# MCU_1_12.net
KiCad netlist of a schematic drawn in Altium Designer
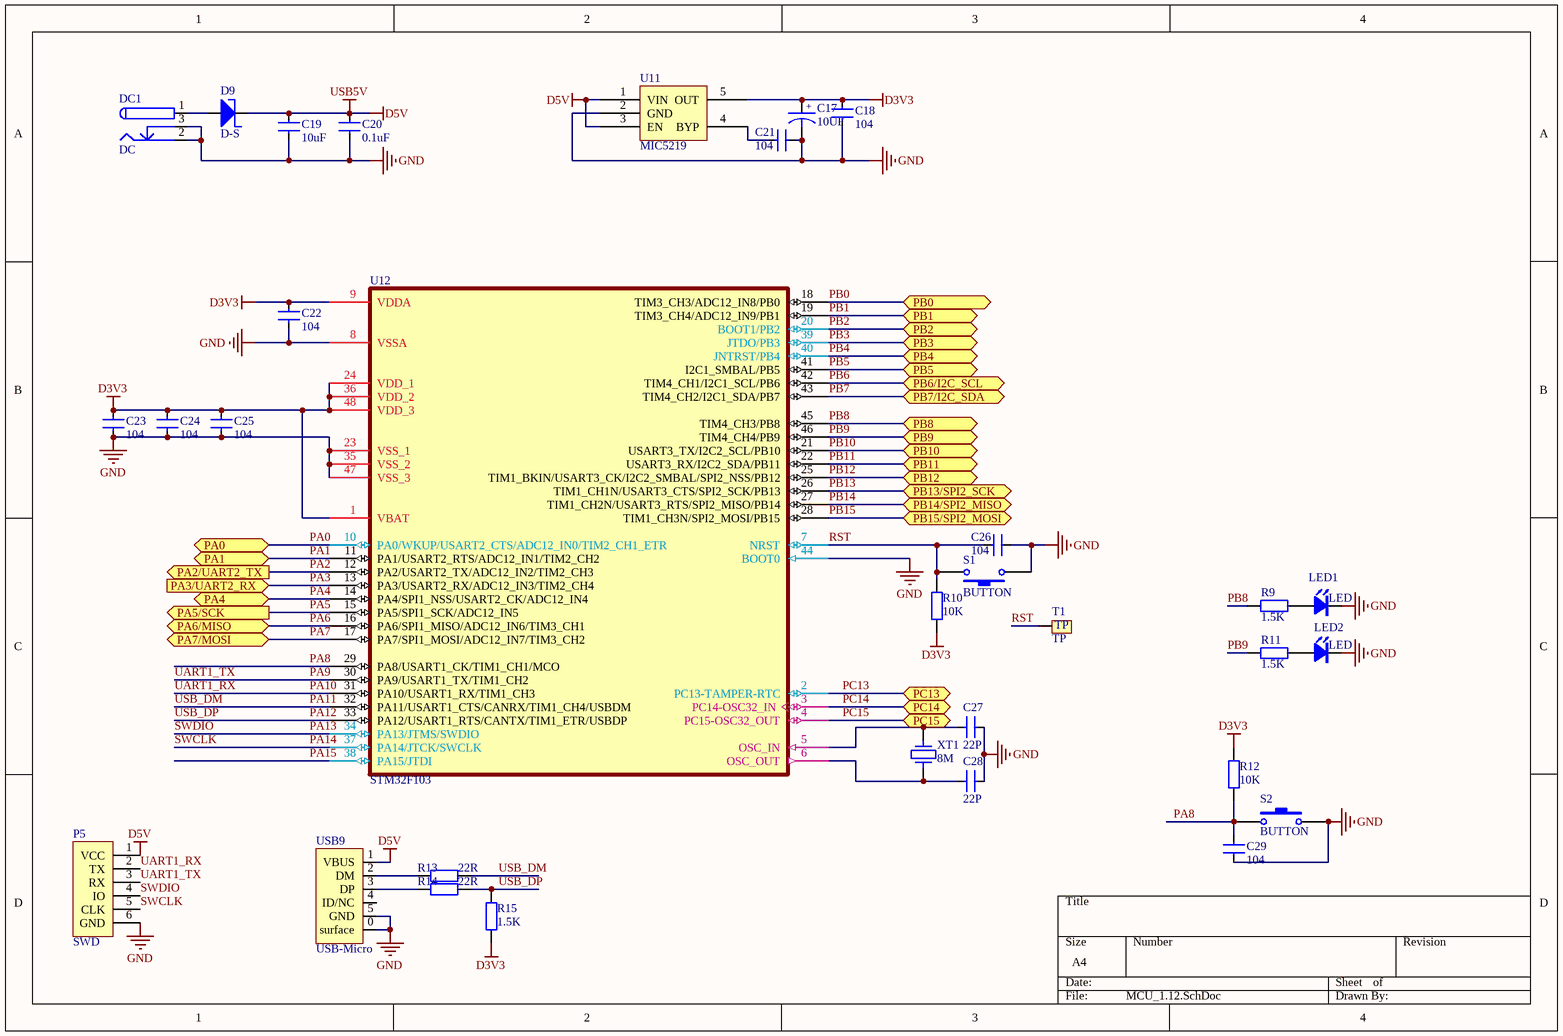
[diagram p0: MCU_1.12.SchDoc]

(export (version "E")
  (design (tool "Eeschema 10.0.6"))
  (components
    (comp (ref "C17")
      (value "10UF")
      (footprint "3216C")
      (description "钽电容")
      (libsource (lib "lib_AD") (part "CAP-T"))
    )
    (comp (ref "C18")
      (value "104")
      (footprint "0603C")
      (description "普通小电容")
      (libsource (lib "lib_GMDZ") (part "CAP"))
    )
    (comp (ref "C19")
      (value "10uF")
      (footprint "0805C")
      (description "普通小电容")
      (libsource (lib "lib_AD") (part "CAP"))
    )
    (comp (ref "C20")
      (value "0.1uF")
      (footprint "0402C")
      (description "普通小电容")
      (libsource (lib "lib_AD") (part "CAP"))
    )
    (comp (ref "C21")
      (value "104")
      (footprint "0603C")
      (description "普通小电容")
      (libsource (lib "lib_GMDZ") (part "CAP"))
    )
    (comp (ref "C22")
      (value "104")
      (footprint "0603C")
      (description "普通小电容")
      (libsource (lib "lib_GMDZ") (part "CAP"))
    )
    (comp (ref "C23")
      (value "104")
      (footprint "0603C")
      (description "普通小电容")
      (libsource (lib "lib_GMDZ") (part "CAP"))
    )
    (comp (ref "C24")
      (value "104")
      (footprint "0603C")
      (description "普通小电容")
      (libsource (lib "lib_GMDZ") (part "CAP"))
    )
    (comp (ref "C25")
      (value "104")
      (footprint "0603C")
      (description "普通小电容")
      (libsource (lib "lib_GMDZ") (part "CAP"))
    )
    (comp (ref "C26")
      (value "104")
      (footprint "0603C")
      (description "普通小电容")
      (libsource (lib "lib_AD") (part "CAP"))
    )
    (comp (ref "C27")
      (value "22P")
      (footprint "0603C")
      (description "普通小电容")
      (libsource (lib "lib_AD") (part "CAP"))
    )
    (comp (ref "C28")
      (value "22P")
      (footprint "0603C")
      (description "普通小电容")
      (libsource (lib "lib_AD") (part "CAP"))
    )
    (comp (ref "C29")
      (value "104")
      (footprint "0603C")
      (description "普通小电容")
      (libsource (lib "lib_AD") (part "CAP"))
    )
    (comp (ref "D9")
      (value "D-S")
      (footprint "SOD123")
      (description "肖特基二极管")
      (libsource (lib "lib_AD") (part "D-S"))
    )
    (comp (ref "DC1")
      (value "DC")
      (footprint "DC005")
      (description "圆形电源接口")
      (libsource (lib "lib_AD") (part "DC00X"))
    )
    (comp (ref "LED1") (value "LED") (footprint "0805D") (libsource (lib "lib_AD") (part "LED")))
    (comp (ref "LED2") (value "LED") (footprint "0805D") (libsource (lib "lib_AD") (part "LED")))
    (comp (ref "P5")
      (value "SWD")
      (footprint "HDR1X6")
      (description "单片机端")
      (libsource (lib "lib_AD") (part "SWD"))
    )
    (comp (ref "R9")
      (value "1.5K")
      (footprint "0603R")
      (description "普通电阻")
      (libsource (lib "lib_AD") (part "RES"))
    )
    (comp (ref "R10")
      (value "10K")
      (footprint "0603R")
      (description "普通电阻")
      (libsource (lib "") (part "RES_1"))
    )
    (comp (ref "R11")
      (value "1.5K")
      (footprint "0603R")
      (description "普通电阻")
      (libsource (lib "lib_AD") (part "RES"))
    )
    (comp (ref "R12")
      (value "10K")
      (footprint "0603R")
      (description "普通电阻")
      (libsource (lib "") (part "RES_3"))
    )
    (comp (ref "R13")
      (value "22R")
      (footprint "0603R")
      (description "普通电阻")
      (libsource (lib "") (part "RES_2"))
    )
    (comp (ref "R14")
      (value "22R")
      (footprint "0603R")
      (description "普通电阻")
      (libsource (lib "") (part "RES_2"))
    )
    (comp (ref "R15")
      (value "1.5K")
      (footprint "0603R")
      (description "普通电阻")
      (libsource (lib "") (part "RES_3"))
    )
    (comp (ref "S1") (value "BUTTON") (footprint "SW-3X4X2") (libsource (lib "lib_AD") (part "BUTTON")))
    (comp (ref "S2") (value "BUTTON") (footprint "SW-3X4X2") (libsource (lib "lib_AD") (part "BUTTON")))
    (comp (ref "T1")
      (value "TP")
      (footprint "TP1")
      (description "testpoint")
      (libsource (lib "lib_AD") (part "TP"))
    )
    (comp (ref "U11") (value "MIC5219") (footprint "SOT23-5") (libsource (lib "lib_GMDZ") (part "MIC5219")))
    (comp (ref "U12")
      (value "STM32F103")
      (footprint "LQFP48")
      (libsource (lib "lib_GMDZ") (part "STM32F103"))
    )
    (comp (ref "USB9")
      (value "USB-Micro")
      (footprint "USB-Micro-2")
      (description "USB 1.1, Right Angle, SMT, A Type, Plug, 4 Position, Natural")
      (fields (field (name "PUBLISHER") "Altium Limited"))
      (libsource (lib "lib_AD") (part "USB-Micro"))
    )
    (comp (ref "XT1")
      (value "8M")
      (footprint "5032")
      (description "晶振")
      (libsource (lib "lib_GMDZ") (part "XT"))
    )
  )
  (nets
    (net (code "4") (name "/PA0") (class "Default")
      (node (ref "U12") (pin "10") (pinfunction "PA0/WKUP/USART2_CTS/ADC12_IN0/TIM2_CH1_ETR_10") (pintype "bidirectional"))
    )
    (net (code "5") (name "/PA1") (class "Default")
      (node (ref "U12") (pin "11") (pinfunction "PA1/USART2_RTS/ADC12_IN1/TIM2_CH2_11") (pintype "bidirectional"))
    )
    (net (code "6") (name "/PA2") (class "Default")
      (node (ref "U12") (pin "12") (pinfunction "PA2/USART2_TX/ADC12_IN2/TIM2_CH3_12") (pintype "bidirectional"))
    )
    (net (code "7") (name "/PA3") (class "Default")
      (node (ref "U12") (pin "13") (pinfunction "PA3/USART2_RX/ADC12_IN3/TIM2_CH4_13") (pintype "bidirectional"))
    )
    (net (code "8") (name "/PA4") (class "Default")
      (node (ref "U12") (pin "14") (pinfunction "PA4/SPI1_NSS/USART2_CK/ADC12_IN4_14") (pintype "bidirectional"))
    )
    (net (code "9") (name "/PA5") (class "Default")
      (node (ref "U12") (pin "15") (pinfunction "PA5/SPI1_SCK/ADC12_IN5_15") (pintype "bidirectional"))
    )
    (net (code "10") (name "/PA6") (class "Default")
      (node (ref "U12") (pin "16") (pinfunction "PA6/SPI1_MISO/ADC12_IN6/TIM3_CH1_16") (pintype "bidirectional"))
    )
    (net (code "11") (name "/PA7") (class "Default")
      (node (ref "U12") (pin "17") (pinfunction "PA7/SPI1_MOSI/ADC12_IN7/TIM3_CH2_17") (pintype "bidirectional"))
    )
    (net (code "12") (name "/PA8") (class "Default")
      (node (ref "C29") (pin "2") (pinfunction "2_2") (pintype "passive"))
      (node (ref "R12") (pin "2") (pinfunction "2_2") (pintype "passive"))
      (node (ref "S2") (pin "1") (pinfunction "1_1") (pintype "passive"))
      (node (ref "U12") (pin "29") (pinfunction "PA8/USART1_CK/TIM1_CH1/MCO_29") (pintype "bidirectional"))
    )
    (net (code "13") (name "/PA9") (class "Default")
      (node (ref "P5") (pin "3") (pinfunction "RX_3") (pintype "passive"))
      (node (ref "U12") (pin "30") (pinfunction "PA9/USART1_TX/TIM1_CH2_30") (pintype "bidirectional"))
    )
    (net (code "14") (name "/PA10") (class "Default")
      (node (ref "P5") (pin "2") (pinfunction "TX_2") (pintype "passive"))
      (node (ref "U12") (pin "31") (pinfunction "PA10/USART1_RX/TIM1_CH3_31") (pintype "bidirectional"))
    )
    (net (code "15") (name "/PA11") (class "Default")
      (node (ref "R13") (pin "1") (pinfunction "1_1") (pintype "passive"))
      (node (ref "U12") (pin "32") (pinfunction "PA11/USART1_CTS/CANRX/TIM1_CH4/USBDM_32") (pintype "bidirectional"))
    )
    (net (code "16") (name "/PA12") (class "Default")
      (node (ref "R14") (pin "1") (pinfunction "1_1") (pintype "passive"))
      (node (ref "R15") (pin "1") (pinfunction "1_1") (pintype "passive"))
      (node (ref "U12") (pin "33") (pinfunction "PA12/USART1_RTS/CANTX/TIM1_ETR/USBDP_33") (pintype "bidirectional"))
    )
    (net (code "17") (name "/PA13") (class "Default")
      (node (ref "P5") (pin "4") (pinfunction "IO_4") (pintype "passive"))
      (node (ref "U12") (pin "34") (pinfunction "PA13/JTMS/SWDIO_34") (pintype "bidirectional"))
    )
    (net (code "18") (name "/PA14") (class "Default")
      (node (ref "P5") (pin "5") (pinfunction "CLK_5") (pintype "passive"))
      (node (ref "U12") (pin "37") (pinfunction "PA14/JTCK/SWCLK_37") (pintype "bidirectional"))
    )
    (net (code "19") (name "/PA15") (class "Default")
      (node (ref "U12") (pin "38") (pinfunction "PA15/JTDI_38") (pintype "bidirectional"))
    )
    (net (code "20") (name "/PB0") (class "Default")
      (node (ref "U12") (pin "18") (pinfunction "TIM3_CH3/ADC12_IN8/PB0_18") (pintype "bidirectional"))
    )
    (net (code "21") (name "/PB1") (class "Default")
      (node (ref "U12") (pin "19") (pinfunction "TIM3_CH4/ADC12_IN9/PB1_19") (pintype "bidirectional"))
    )
    (net (code "22") (name "/PB2") (class "Default")
      (node (ref "U12") (pin "20") (pinfunction "BOOT1/PB2_20") (pintype "bidirectional"))
    )
    (net (code "23") (name "/PB3") (class "Default")
      (node (ref "U12") (pin "39") (pinfunction "JTDO/PB3_39") (pintype "bidirectional"))
    )
    (net (code "24") (name "/PB4") (class "Default")
      (node (ref "U12") (pin "40") (pinfunction "JNTRST/PB4_40") (pintype "bidirectional"))
    )
    (net (code "25") (name "/PB5") (class "Default")
      (node (ref "U12") (pin "41") (pinfunction "I2C1_SMBAL/PB5_41") (pintype "bidirectional"))
    )
    (net (code "26") (name "/PB6") (class "Default")
      (node (ref "U12") (pin "42") (pinfunction "TIM4_CH1/I2C1_SCL/PB6_42") (pintype "bidirectional"))
    )
    (net (code "27") (name "/PB7") (class "Default")
      (node (ref "U12") (pin "43") (pinfunction "TIM4_CH2/I2C1_SDA/PB7_43") (pintype "bidirectional"))
    )
    (net (code "28") (name "/PB8") (class "Default")
      (node (ref "R9") (pin "1") (pinfunction "1_1") (pintype "passive"))
      (node (ref "U12") (pin "45") (pinfunction "TIM4_CH3/PB8_45") (pintype "bidirectional"))
    )
    (net (code "29") (name "/PB9") (class "Default")
      (node (ref "R11") (pin "1") (pinfunction "1_1") (pintype "passive"))
      (node (ref "U12") (pin "46") (pinfunction "TIM4_CH4/PB9_46") (pintype "bidirectional"))
    )
    (net (code "30") (name "/PB10") (class "Default")
      (node (ref "U12") (pin "21") (pinfunction "USART3_TX/I2C2_SCL/PB10_21") (pintype "bidirectional"))
    )
    (net (code "31") (name "/PB11") (class "Default")
      (node (ref "U12") (pin "22") (pinfunction "USART3_RX/I2C2_SDA/PB11_22") (pintype "bidirectional"))
    )
    (net (code "32") (name "/PB12") (class "Default")
      (node (ref "U12") (pin "25") (pinfunction "TIM1_BKIN/USART3_CK/I2C2_SMBAL/SPI2_NSS/PB12_25") (pintype "bidirectional"))
    )
    (net (code "33") (name "/PB13") (class "Default")
      (node (ref "U12") (pin "26") (pinfunction "TIM1_CH1N/USART3_CTS/SPI2_SCK/PB13_26") (pintype "bidirectional"))
    )
    (net (code "34") (name "/PB14") (class "Default")
      (node (ref "U12") (pin "27") (pinfunction "TIM1_CH2N/USART3_RTS/SPI2_MISO/PB14_27") (pintype "bidirectional"))
    )
    (net (code "35") (name "/PB15") (class "Default")
      (node (ref "U12") (pin "28") (pinfunction "TIM1_CH3N/SPI2_MOSI/PB15_28") (pintype "bidirectional"))
    )
    (net (code "36") (name "/PC13") (class "Default")
      (node (ref "U12") (pin "2") (pinfunction "PC13-TAMPER-RTC_2") (pintype "bidirectional"))
    )
    (net (code "37") (name "/PC14") (class "Default")
      (node (ref "U12") (pin "3") (pinfunction "PC14-OSC32_IN_3") (pintype "bidirectional"))
    )
    (net (code "38") (name "/PC15") (class "Default")
      (node (ref "U12") (pin "4") (pinfunction "PC15-OSC32_OUT_4") (pintype "bidirectional"))
    )
    (net (code "39") (name "/RST") (class "Default")
      (node (ref "C26") (pin "1") (pinfunction "1_1") (pintype "passive"))
      (node (ref "R10") (pin "2") (pinfunction "2_2") (pintype "passive"))
      (node (ref "S1") (pin "2") (pinfunction "2_2") (pintype "passive"))
      (node (ref "T1") (pin "1") (pinfunction "1_1") (pintype "passive"))
      (node (ref "U12") (pin "7") (pinfunction "NRST_7") (pintype "bidirectional"))
    )
    (net (code "40") (name "D3V3") (class "Default")
      (node (ref "C17") (pin "1") (pinfunction "1_1") (pintype "passive"))
      (node (ref "C18") (pin "2") (pinfunction "2_2") (pintype "passive"))
      (node (ref "C22") (pin "2") (pinfunction "2_2") (pintype "passive"))
      (node (ref "C23") (pin "2") (pinfunction "2_2") (pintype "passive"))
      (node (ref "C24") (pin "1") (pinfunction "1_1") (pintype "passive"))
      (node (ref "C25") (pin "2") (pinfunction "2_2") (pintype "passive"))
      (node (ref "R10") (pin "1") (pinfunction "1_1") (pintype "passive"))
      (node (ref "R12") (pin "1") (pinfunction "1_1") (pintype "passive"))
      (node (ref "R15") (pin "2") (pinfunction "2_2") (pintype "passive"))
      (node (ref "U11") (pin "5") (pinfunction "OUT_5") (pintype "passive"))
      (node (ref "U12") (pin "1") (pinfunction "VBAT_1") (pintype "power_in"))
      (node (ref "U12") (pin "24") (pinfunction "VDD_1_24") (pintype "power_in"))
      (node (ref "U12") (pin "36") (pinfunction "VDD_2_36") (pintype "power_in"))
      (node (ref "U12") (pin "48") (pinfunction "VDD_3_48") (pintype "power_in"))
      (node (ref "U12") (pin "9") (pinfunction "VDDA_9") (pintype "power_in"))
    )
    (net (code "41") (name "D5V") (class "Default")
      (node (ref "C19") (pin "1") (pinfunction "1_1") (pintype "passive"))
      (node (ref "C20") (pin "1") (pinfunction "1_1") (pintype "passive"))
      (node (ref "D9") (pin "K") (pinfunction "2_K") (pintype "passive"))
      (node (ref "P5") (pin "1") (pinfunction "VCC_1") (pintype "passive"))
      (node (ref "U11") (pin "1") (pinfunction "VIN_1") (pintype "passive"))
      (node (ref "U11") (pin "3") (pinfunction "EN_3") (pintype "passive"))
      (node (ref "USB9") (pin "1") (pinfunction "VBUS_1") (pintype "power_in"))
    )
    (net (code "42") (name "GND") (class "Default")
      (node (ref "C17") (pin "2") (pinfunction "2_2") (pintype "passive"))
      (node (ref "C18") (pin "1") (pinfunction "1_1") (pintype "passive"))
      (node (ref "C19") (pin "2") (pinfunction "2_2") (pintype "passive"))
      (node (ref "C20") (pin "2") (pinfunction "2_2") (pintype "passive"))
      (node (ref "C21") (pin "2") (pinfunction "2_2") (pintype "passive"))
      (node (ref "C22") (pin "1") (pinfunction "1_1") (pintype "passive"))
      (node (ref "C23") (pin "1") (pinfunction "1_1") (pintype "passive"))
      (node (ref "C24") (pin "2") (pinfunction "2_2") (pintype "passive"))
      (node (ref "C25") (pin "1") (pinfunction "1_1") (pintype "passive"))
      (node (ref "C26") (pin "2") (pinfunction "2_2") (pintype "passive"))
      (node (ref "C27") (pin "2") (pinfunction "2_2") (pintype "passive"))
      (node (ref "C28") (pin "2") (pinfunction "2_2") (pintype "passive"))
      (node (ref "C29") (pin "1") (pinfunction "1_1") (pintype "passive"))
      (node (ref "DC1") (pin "2") (pinfunction "2_2") (pintype "power_in"))
      (node (ref "DC1") (pin "3") (pinfunction "3_3") (pintype "power_in"))
      (node (ref "LED1") (pin "K") (pinfunction "2_K") (pintype "passive"))
      (node (ref "LED2") (pin "K") (pinfunction "2_K") (pintype "passive"))
      (node (ref "P5") (pin "6") (pinfunction "GND_6") (pintype "passive"))
      (node (ref "S1") (pin "1") (pinfunction "1_1") (pintype "passive"))
      (node (ref "S2") (pin "2") (pinfunction "2_2") (pintype "passive"))
      (node (ref "U11") (pin "2") (pinfunction "GND_2") (pintype "passive"))
      (node (ref "U12") (pin "23") (pinfunction "VSS_1_23") (pintype "power_in"))
      (node (ref "U12") (pin "35") (pinfunction "VSS_2_35") (pintype "power_in"))
      (node (ref "U12") (pin "44") (pinfunction "BOOT0_44") (pintype "input"))
      (node (ref "U12") (pin "47") (pinfunction "VSS_3_47") (pintype "power_in"))
      (node (ref "U12") (pin "8") (pinfunction "VSSA_8") (pintype "power_in"))
      (node (ref "USB9") (pin "0") (pinfunction "surface_0") (pintype "passive"))
      (node (ref "USB9") (pin "5") (pinfunction "GND_5") (pintype "power_in"))
    )
    (net (code "43") (name "Net-(D9-1)") (class "Default")
      (node (ref "D9") (pin "A") (pinfunction "1_A") (pintype "passive"))
      (node (ref "DC1") (pin "1") (pinfunction "1_1") (pintype "power_in"))
    )
    (net (code "44") (name "Net-(LED1-1)") (class "Default")
      (node (ref "LED1") (pin "A") (pinfunction "1_A") (pintype "passive"))
      (node (ref "R9") (pin "2") (pinfunction "2_2") (pintype "passive"))
    )
    (net (code "45") (name "Net-(LED2-1)") (class "Default")
      (node (ref "LED2") (pin "A") (pinfunction "1_A") (pintype "passive"))
      (node (ref "R11") (pin "2") (pinfunction "2_2") (pintype "passive"))
    )
    (net (code "46") (name "Net-(U11-BYP)") (class "Default")
      (node (ref "C21") (pin "1") (pinfunction "1_1") (pintype "passive"))
      (node (ref "U11") (pin "4") (pinfunction "BYP_4") (pintype "passive"))
    )
    (net (code "47") (name "Net-(U12-OSC_IN)") (class "Default")
      (node (ref "C27") (pin "1") (pinfunction "1_1") (pintype "passive"))
      (node (ref "U12") (pin "5") (pinfunction "OSC_IN_5") (pintype "input"))
      (node (ref "XT1") (pin "1") (pinfunction "1_1") (pintype "passive"))
    )
    (net (code "48") (name "Net-(U12-OSC_OUT)") (class "Default")
      (node (ref "C28") (pin "1") (pinfunction "1_1") (pintype "passive"))
      (node (ref "U12") (pin "6") (pinfunction "OSC_OUT_6") (pintype "output"))
      (node (ref "XT1") (pin "2") (pinfunction "2_2") (pintype "passive"))
    )
    (net (code "49") (name "Net-(USB9-DM)") (class "Default")
      (node (ref "R13") (pin "2") (pinfunction "2_2") (pintype "passive"))
      (node (ref "USB9") (pin "2") (pinfunction "DM_2") (pintype "passive"))
    )
    (net (code "50") (name "Net-(USB9-DP)") (class "Default")
      (node (ref "R14") (pin "2") (pinfunction "2_2") (pintype "passive"))
      (node (ref "USB9") (pin "3") (pinfunction "DP_3") (pintype "passive"))
    )
    (net (code "51") (name "unconnected-(USB9-ID{slash}NC-Pad4)") (class "Default")
      (node (ref "USB9") (pin "4") (pinfunction "ID/NC_4") (pintype "passive"))
    )
  )
)
